# 1_P1.net
KiCad netlist of a schematic drawn in Altium Designer
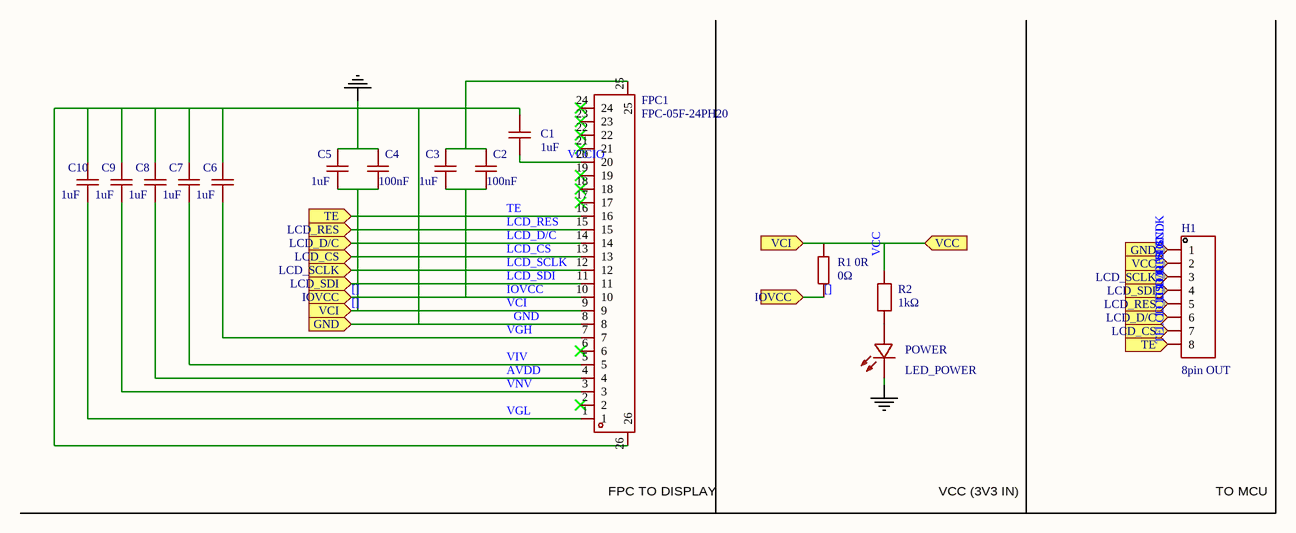
[diagram p0: 1_P1.schdoc]

(export (version "E")
  (design (tool "Eeschema 10.0.6"))
  (components
    (comp (ref "C1")
      (value "1uF")
      (footprint "C0603")
      (description "容值:1uF;精度:±10%;额定电压:25V;温度系数:X7R;")
      (fields
        (field (name "MANUFACTURER") "SAMSUNG(三星)")
        (field (name "MANUFACTURER PART") "CL10B105KA8NNNC")
      )
      (libsource (lib "altium-import") (part "root_1_CL10B105KA8NNNC_"))
    )
    (comp (ref "C2")
      (value "100nF")
      (footprint "C0603")
      (description "容值:100nF;精度:±10%;额定电压:50V;温度系数:X7R;")
      (fields (field (name "MANUFACTURER") "FH(风华)") (field (name "MANUFACTURER PART") "0603B104K500NT"))
      (libsource (lib "altium-import") (part "root_1_0603B104K500NT_"))
    )
    (comp (ref "C3")
      (value "1uF")
      (footprint "C0603")
      (description "容值:1uF;精度:±10%;额定电压:25V;温度系数:X7R;")
      (fields
        (field (name "MANUFACTURER") "SAMSUNG(三星)")
        (field (name "MANUFACTURER PART") "CL10B105KA8NNNC")
      )
      (libsource (lib "altium-import") (part "root_1_CL10B105KA8NNNC_"))
    )
    (comp (ref "C4")
      (value "100nF")
      (footprint "C0603")
      (description "容值:100nF;精度:±10%;额定电压:50V;温度系数:X7R;")
      (fields (field (name "MANUFACTURER") "FH(风华)") (field (name "MANUFACTURER PART") "0603B104K500NT"))
      (libsource (lib "altium-import") (part "root_1_0603B104K500NT_"))
    )
    (comp (ref "C5")
      (value "1uF")
      (footprint "C0603")
      (description "容值:1uF;精度:±10%;额定电压:25V;温度系数:X7R;")
      (fields
        (field (name "MANUFACTURER") "SAMSUNG(三星)")
        (field (name "MANUFACTURER PART") "CL10B105KA8NNNC")
      )
      (libsource (lib "altium-import") (part "root_1_CL10B105KA8NNNC_"))
    )
    (comp (ref "C6")
      (value "1uF")
      (footprint "C0603")
      (description "容值:1uF;精度:±10%;额定电压:25V;温度系数:X7R;")
      (fields
        (field (name "MANUFACTURER") "SAMSUNG(三星)")
        (field (name "MANUFACTURER PART") "CL10B105KA8NNNC")
      )
      (libsource (lib "altium-import") (part "root_1_CL10B105KA8NNNC_"))
    )
    (comp (ref "C7")
      (value "1uF")
      (footprint "C0603")
      (description "容值:1uF;精度:±10%;额定电压:25V;温度系数:X7R;")
      (fields
        (field (name "MANUFACTURER") "SAMSUNG(三星)")
        (field (name "MANUFACTURER PART") "CL10B105KA8NNNC")
      )
      (libsource (lib "altium-import") (part "root_1_CL10B105KA8NNNC_"))
    )
    (comp (ref "C8")
      (value "1uF")
      (footprint "C0603")
      (description "容值:1uF;精度:±10%;额定电压:25V;温度系数:X7R;")
      (fields
        (field (name "MANUFACTURER") "SAMSUNG(三星)")
        (field (name "MANUFACTURER PART") "CL10B105KA8NNNC")
      )
      (libsource (lib "altium-import") (part "root_1_CL10B105KA8NNNC_"))
    )
    (comp (ref "C9")
      (value "1uF")
      (footprint "C0603")
      (description "容值:1uF;精度:±10%;额定电压:25V;温度系数:X7R;")
      (fields
        (field (name "MANUFACTURER") "SAMSUNG(三星)")
        (field (name "MANUFACTURER PART") "CL10B105KA8NNNC")
      )
      (libsource (lib "altium-import") (part "root_1_CL10B105KA8NNNC_"))
    )
    (comp (ref "C10")
      (value "1uF")
      (footprint "C0603")
      (description "容值:1uF;精度:±10%;额定电压:25V;温度系数:X7R;")
      (fields
        (field (name "MANUFACTURER") "SAMSUNG(三星)")
        (field (name "MANUFACTURER PART") "CL10B105KA8NNNC")
      )
      (libsource (lib "altium-import") (part "root_1_CL10B105KA8NNNC_"))
    )
    (comp (ref "FPC1")
      (value "FPC-05F-24PH20")
      (footprint "FPC-SMD_24P-P0.50_FPC-05F-24PH20")
      (description "锁定特性:翻盖式;触点类型:卧贴;触点数量:24P;间距:0.5mm;安装方式:下接;工作温度:-25℃~+85℃;")
      (fields (field (name "MANUFACTURER") "XUNPU(讯普)"))
      (libsource (lib "altium-import") (part "root_2_mirrored_FPC-05F-24PH20_"))
    )
    (comp (ref "H1")
      (value "8pin OUT")
      (footprint "HDR-TH_8P-P2.54-V-M")
      (fields (field (name "MANUFACTURER") "Ckmtw(灿科盟)"))
      (libsource (lib "altium-import") (part "root_0_B-2100S08P-A110_"))
    )
    (comp (ref "POWER")
      (value "LED_POWER")
      (footprint "LED0603-RD-YELLOW")
      (fields (field (name "MANUFACTURER") "LITEON(光宝)"))
      (libsource (lib "altium-import") (part "root_1_LTST-C191KSKT_"))
    )
    (comp (ref "R1 0R")
      (value "0Ω")
      (footprint "R0805")
      (description "电阻类型:厚膜电阻;阻值:0Ω;精度:±1%;功率:125mW;工作电压:150V;温度系数:±800ppm/℃;")
      (fields
        (field (name "MANUFACTURER") "UNI-ROYAL(厚声)")
        (field (name "MANUFACTURER PART") "0805W8F0000T5E")
      )
      (libsource (lib "altium-import") (part "root_1_0805W8F0000T5E_"))
    )
    (comp (ref "R2")
      (value "1kΩ")
      (footprint "R0805")
      (description "电阻类型:厚膜电阻;阻值:1kΩ;精度:±5%;功率:125mW;工作电压:150V;温度系数:±100ppm/℃;")
      (fields (field (name "MANUFACTURER") "FOJAN(富捷)") (field (name "MANUFACTURER PART") "FRR0805J102 TS"))
      (libsource (lib "altium-import") (part "root_1_FRR0805J102 TS_"))
    )
  )
  (nets
    (net (code "1") (name "/AVDD") (class "Default")
      (node (ref "C8") (pin "1") (pinfunction "1_1") (pintype "passive"))
      (node (ref "FPC1") (pin "4") (pinfunction "4_4") (pintype "passive"))
    )
    (net (code "2") (name "/IOVCC") (class "Default")
      (node (ref "C2") (pin "1") (pinfunction "1_1") (pintype "passive"))
      (node (ref "C3") (pin "1") (pinfunction "1_1") (pintype "passive"))
      (node (ref "C4") (pin "1") (pinfunction "1_1") (pintype "passive"))
      (node (ref "C5") (pin "1") (pinfunction "1_1") (pintype "passive"))
      (node (ref "FPC1") (pin "10") (pinfunction "10_10") (pintype "passive"))
      (node (ref "FPC1") (pin "9") (pinfunction "9_9") (pintype "passive"))
      (node (ref "H1") (pin "2") (pinfunction "2_2") (pintype "passive"))
      (node (ref "R1 0R") (pin "1") (pinfunction "1_1") (pintype "passive"))
      (node (ref "R1 0R") (pin "2") (pinfunction "2_2") (pintype "passive"))
      (node (ref "R2") (pin "2") (pinfunction "2_2") (pintype "passive"))
    )
    (net (code "3") (name "/LCD_CS") (class "Default")
      (node (ref "FPC1") (pin "13") (pinfunction "13_13") (pintype "passive"))
      (node (ref "H1") (pin "7") (pinfunction "7_7") (pintype "passive"))
    )
    (net (code "4") (name "/LCD_D{slash}C") (class "Default")
      (node (ref "FPC1") (pin "14") (pinfunction "14_14") (pintype "passive"))
      (node (ref "H1") (pin "6") (pinfunction "6_6") (pintype "passive"))
    )
    (net (code "5") (name "/LCD_RES") (class "Default")
      (node (ref "FPC1") (pin "15") (pinfunction "15_15") (pintype "passive"))
      (node (ref "H1") (pin "5") (pinfunction "5_5") (pintype "passive"))
    )
    (net (code "6") (name "/LCD_SCLK") (class "Default")
      (node (ref "FPC1") (pin "12") (pinfunction "12_12") (pintype "passive"))
      (node (ref "H1") (pin "3") (pinfunction "3_3") (pintype "passive"))
    )
    (net (code "7") (name "/LCD_SDI") (class "Default")
      (node (ref "FPC1") (pin "11") (pinfunction "11_11") (pintype "passive"))
      (node (ref "H1") (pin "4") (pinfunction "4_4") (pintype "passive"))
    )
    (net (code "8") (name "/TE") (class "Default")
      (node (ref "FPC1") (pin "16") (pinfunction "16_16") (pintype "passive"))
      (node (ref "H1") (pin "8") (pinfunction "8_8") (pintype "passive"))
    )
    (net (code "9") (name "/VCCIO") (class "Default")
      (node (ref "C1") (pin "1") (pinfunction "1_1") (pintype "passive"))
      (node (ref "FPC1") (pin "20") (pinfunction "20_20") (pintype "passive"))
    )
    (net (code "10") (name "/VGH") (class "Default")
      (node (ref "C6") (pin "1") (pinfunction "1_1") (pintype "passive"))
      (node (ref "FPC1") (pin "7") (pinfunction "7_7") (pintype "passive"))
    )
    (net (code "11") (name "/VGL") (class "Default")
      (node (ref "C10") (pin "1") (pinfunction "1_1") (pintype "passive"))
      (node (ref "FPC1") (pin "1") (pinfunction "1_1") (pintype "passive"))
    )
    (net (code "12") (name "/VIV") (class "Default")
      (node (ref "C7") (pin "1") (pinfunction "1_1") (pintype "passive"))
      (node (ref "FPC1") (pin "5") (pinfunction "5_5") (pintype "passive"))
    )
    (net (code "13") (name "/VNV") (class "Default")
      (node (ref "C9") (pin "1") (pinfunction "1_1") (pintype "passive"))
      (node (ref "FPC1") (pin "3") (pinfunction "3_3") (pintype "passive"))
    )
    (net (code "14") (name "GND") (class "Default")
      (node (ref "C1") (pin "2") (pinfunction "2_2") (pintype "passive"))
      (node (ref "C10") (pin "2") (pinfunction "2_2") (pintype "passive"))
      (node (ref "C2") (pin "2") (pinfunction "2_2") (pintype "passive"))
      (node (ref "C3") (pin "2") (pinfunction "2_2") (pintype "passive"))
      (node (ref "C4") (pin "2") (pinfunction "2_2") (pintype "passive"))
      (node (ref "C5") (pin "2") (pinfunction "2_2") (pintype "passive"))
      (node (ref "C6") (pin "2") (pinfunction "2_2") (pintype "passive"))
      (node (ref "C7") (pin "2") (pinfunction "2_2") (pintype "passive"))
      (node (ref "C8") (pin "2") (pinfunction "2_2") (pintype "passive"))
      (node (ref "C9") (pin "2") (pinfunction "2_2") (pintype "passive"))
      (node (ref "FPC1") (pin "25") (pinfunction "25_25") (pintype "passive"))
      (node (ref "FPC1") (pin "26") (pinfunction "26_26") (pintype "passive"))
      (node (ref "FPC1") (pin "8") (pinfunction "8_8") (pintype "passive"))
      (node (ref "H1") (pin "1") (pinfunction "1_1") (pintype "passive"))
      (node (ref "POWER") (pin "1") (pinfunction "-_1") (pintype "passive"))
    )
    (net (code "15") (name "Net-(POWER-+)") (class "Default")
      (node (ref "POWER") (pin "2") (pinfunction "+_2") (pintype "passive"))
      (node (ref "R2") (pin "1") (pinfunction "1_1") (pintype "passive"))
    )
    (net (code "16") (name "unconnected-(FPC1-Pad2)") (class "Default")
      (node (ref "FPC1") (pin "2") (pinfunction "2_2") (pintype "passive+no_connect"))
    )
    (net (code "17") (name "unconnected-(FPC1-Pad6)") (class "Default")
      (node (ref "FPC1") (pin "6") (pinfunction "6_6") (pintype "passive+no_connect"))
    )
    (net (code "18") (name "unconnected-(FPC1-Pad17)") (class "Default")
      (node (ref "FPC1") (pin "17") (pinfunction "17_17") (pintype "passive+no_connect"))
    )
    (net (code "19") (name "unconnected-(FPC1-Pad18)") (class "Default")
      (node (ref "FPC1") (pin "18") (pinfunction "18_18") (pintype "passive+no_connect"))
    )
    (net (code "20") (name "unconnected-(FPC1-Pad19)") (class "Default")
      (node (ref "FPC1") (pin "19") (pinfunction "19_19") (pintype "passive+no_connect"))
    )
    (net (code "21") (name "unconnected-(FPC1-Pad21)") (class "Default")
      (node (ref "FPC1") (pin "21") (pinfunction "21_21") (pintype "passive+no_connect"))
    )
    (net (code "22") (name "unconnected-(FPC1-Pad22)") (class "Default")
      (node (ref "FPC1") (pin "22") (pinfunction "22_22") (pintype "passive+no_connect"))
    )
    (net (code "23") (name "unconnected-(FPC1-Pad23)") (class "Default")
      (node (ref "FPC1") (pin "23") (pinfunction "23_23") (pintype "passive+no_connect"))
    )
    (net (code "24") (name "unconnected-(FPC1-Pad24)") (class "Default")
      (node (ref "FPC1") (pin "24") (pinfunction "24_24") (pintype "passive+no_connect"))
    )
  )
)
